# Power_-_5V0.net
KiCad netlist of a schematic drawn in Altium Designer
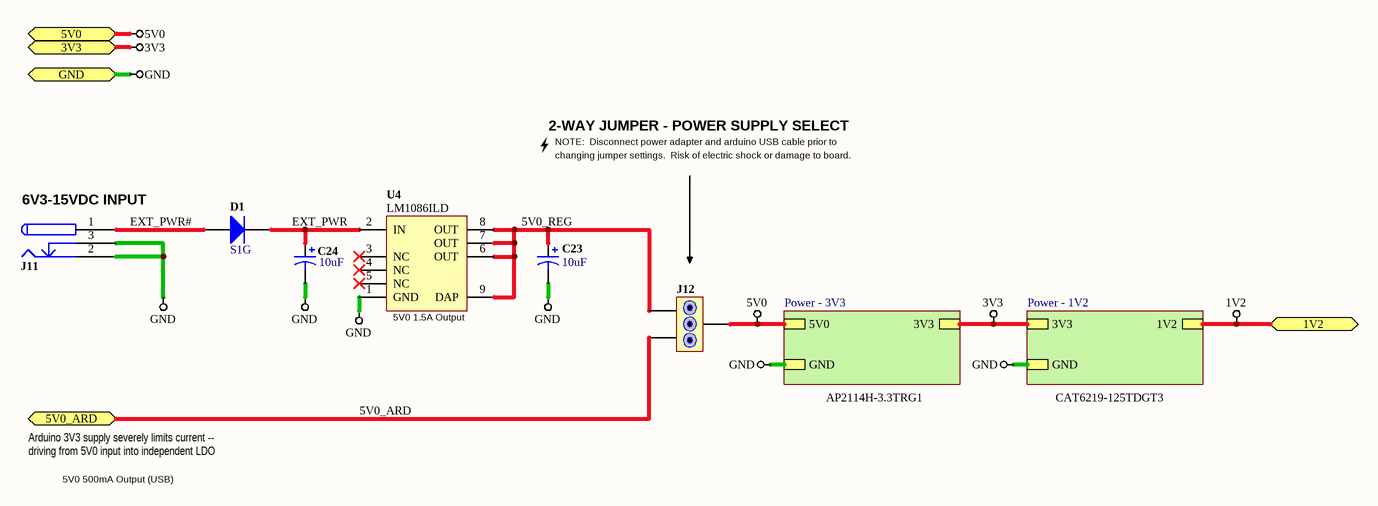
[diagram p0: Power - 5V0.SchDoc]

(export (version "E")
  (design (tool "Eeschema 10.0.6"))
  (components
    (comp (ref "C23")
      (value "TAJB106K020R")
      (footprint "AVX-CAPC3528_V")
      (description "Capacitor, Tantalum, 10uF 10% 20V MCCT-B (3528)")
      (fields
        (field (name "CAPACITANCE") "10uF")
        (field (name "MANUFACTURER") "AVX")
        (field (name "TOLERANCE") "10%")
      )
      (libsource (lib "Altium Content Vault") (part "CMP-0279-00001-1"))
    )
    (comp (ref "C24")
      (value "TAJB106K020R")
      (footprint "AVX-CAPC3528_V")
      (description "Capacitor, Tantalum, 10uF 10% 20V MCCT-B (3528)")
      (fields
        (field (name "CAPACITANCE") "10uF")
        (field (name "MANUFACTURER") "AVX")
        (field (name "TOLERANCE") "10%")
      )
      (libsource (lib "Altium Content Vault") (part "CMP-0279-00001-1"))
    )
    (comp (ref "D1")
      (value "S1G")
      (footprint "DO-214AC")
      (description "Fairchild S1G General Purpose Rectifier")
      (libsource (lib "DIODE-S1G") (part "S1G"))
    )
    (comp (ref "J11")
      (value "PWR CONNECTOR")
      (footprint "KLD-0202")
      (description "Connector, 3 Conductor Power Jack")
      (libsource (lib "PWR_CONNECTOR_3") (part "POWER-CONNECTOR-3"))
    )
    (comp (ref "J12")
      (value "3-WAY JUMPER")
      (footprint "HDR1X3")
      (description "3-Way Jumper - Center Output")
      (libsource (lib "3-WAY JUMPER") (part "3-WAY JUMPER"))
    )
    (comp (ref "U4")
      (value "LM1086ILD-3.3/NOPB")
      (footprint "LDC08A")
      (description "1.5A Low Dropout Positive Regulators, 8-pin LLP, Pb-Free")
      (fields
        (field (name "MANUFACTURER") "National Semiconductor")
        (field (name "ABBREVIATED NAME") "LM1086ILD")
      )
      (libsource (lib "Altium Content Vault") (part "CMP-0062-01489-2"))
    )
  )
  (nets
    (net (code "1") (name "/5V0_ARD") (class "Default")
      (node (ref "J12") (pin "3") (pinfunction "3_3") (pintype "passive"))
    )
    (net (code "2") (name "/5V0_REG") (class "Default")
      (node (ref "C23") (pin "1") (pinfunction "1_1") (pintype "passive"))
      (node (ref "J12") (pin "1") (pinfunction "1_1") (pintype "passive"))
      (node (ref "U4") (pin "6") (pinfunction "OUT_6") (pintype "power_in"))
      (node (ref "U4") (pin "7") (pinfunction "OUT_7") (pintype "power_in"))
      (node (ref "U4") (pin "8") (pinfunction "OUT_8") (pintype "power_in"))
      (node (ref "U4") (pin "9") (pinfunction "DAP_9") (pintype "power_in"))
    )
    (net (code "3") (name "/EXT_PWR") (class "Default")
      (node (ref "C24") (pin "1") (pinfunction "1_1") (pintype "passive"))
      (node (ref "D1") (pin "2") (pinfunction "2_2") (pintype "passive"))
      (node (ref "U4") (pin "2") (pinfunction "IN_2") (pintype "power_in"))
    )
    (net (code "4") (name "/EXT_PWR#") (class "Default")
      (node (ref "D1") (pin "1") (pinfunction "1_1") (pintype "passive"))
      (node (ref "J11") (pin "1") (pintype "power_in"))
    )
    (net (code "7") (name "5V0") (class "Default")
      (node (ref "J12") (pin "2") (pinfunction "2_2") (pintype "passive"))
    )
    (net (code "8") (name "GND") (class "Default")
      (node (ref "C23") (pin "2") (pinfunction "2_2") (pintype "passive"))
      (node (ref "C24") (pin "2") (pinfunction "2_2") (pintype "passive"))
      (node (ref "J11") (pin "2") (pintype "power_in"))
      (node (ref "J11") (pin "3") (pintype "power_in"))
      (node (ref "U4") (pin "1") (pinfunction "GND_1") (pintype "power_in"))
    )
    (net (code "9") (name "unconnected-(U4-NC-Pad3)") (class "Default")
      (node (ref "U4") (pin "3") (pinfunction "NC_3") (pintype "passive+no_connect"))
    )
    (net (code "10") (name "unconnected-(U4-NC-Pad4)") (class "Default")
      (node (ref "U4") (pin "4") (pinfunction "NC_4") (pintype "passive+no_connect"))
    )
    (net (code "11") (name "unconnected-(U4-NC-Pad5)") (class "Default")
      (node (ref "U4") (pin "5") (pinfunction "NC_5") (pintype "passive+no_connect"))
    )
  )
)
